# Nano103.net
KiCad netlist of a schematic drawn in Altium Designer
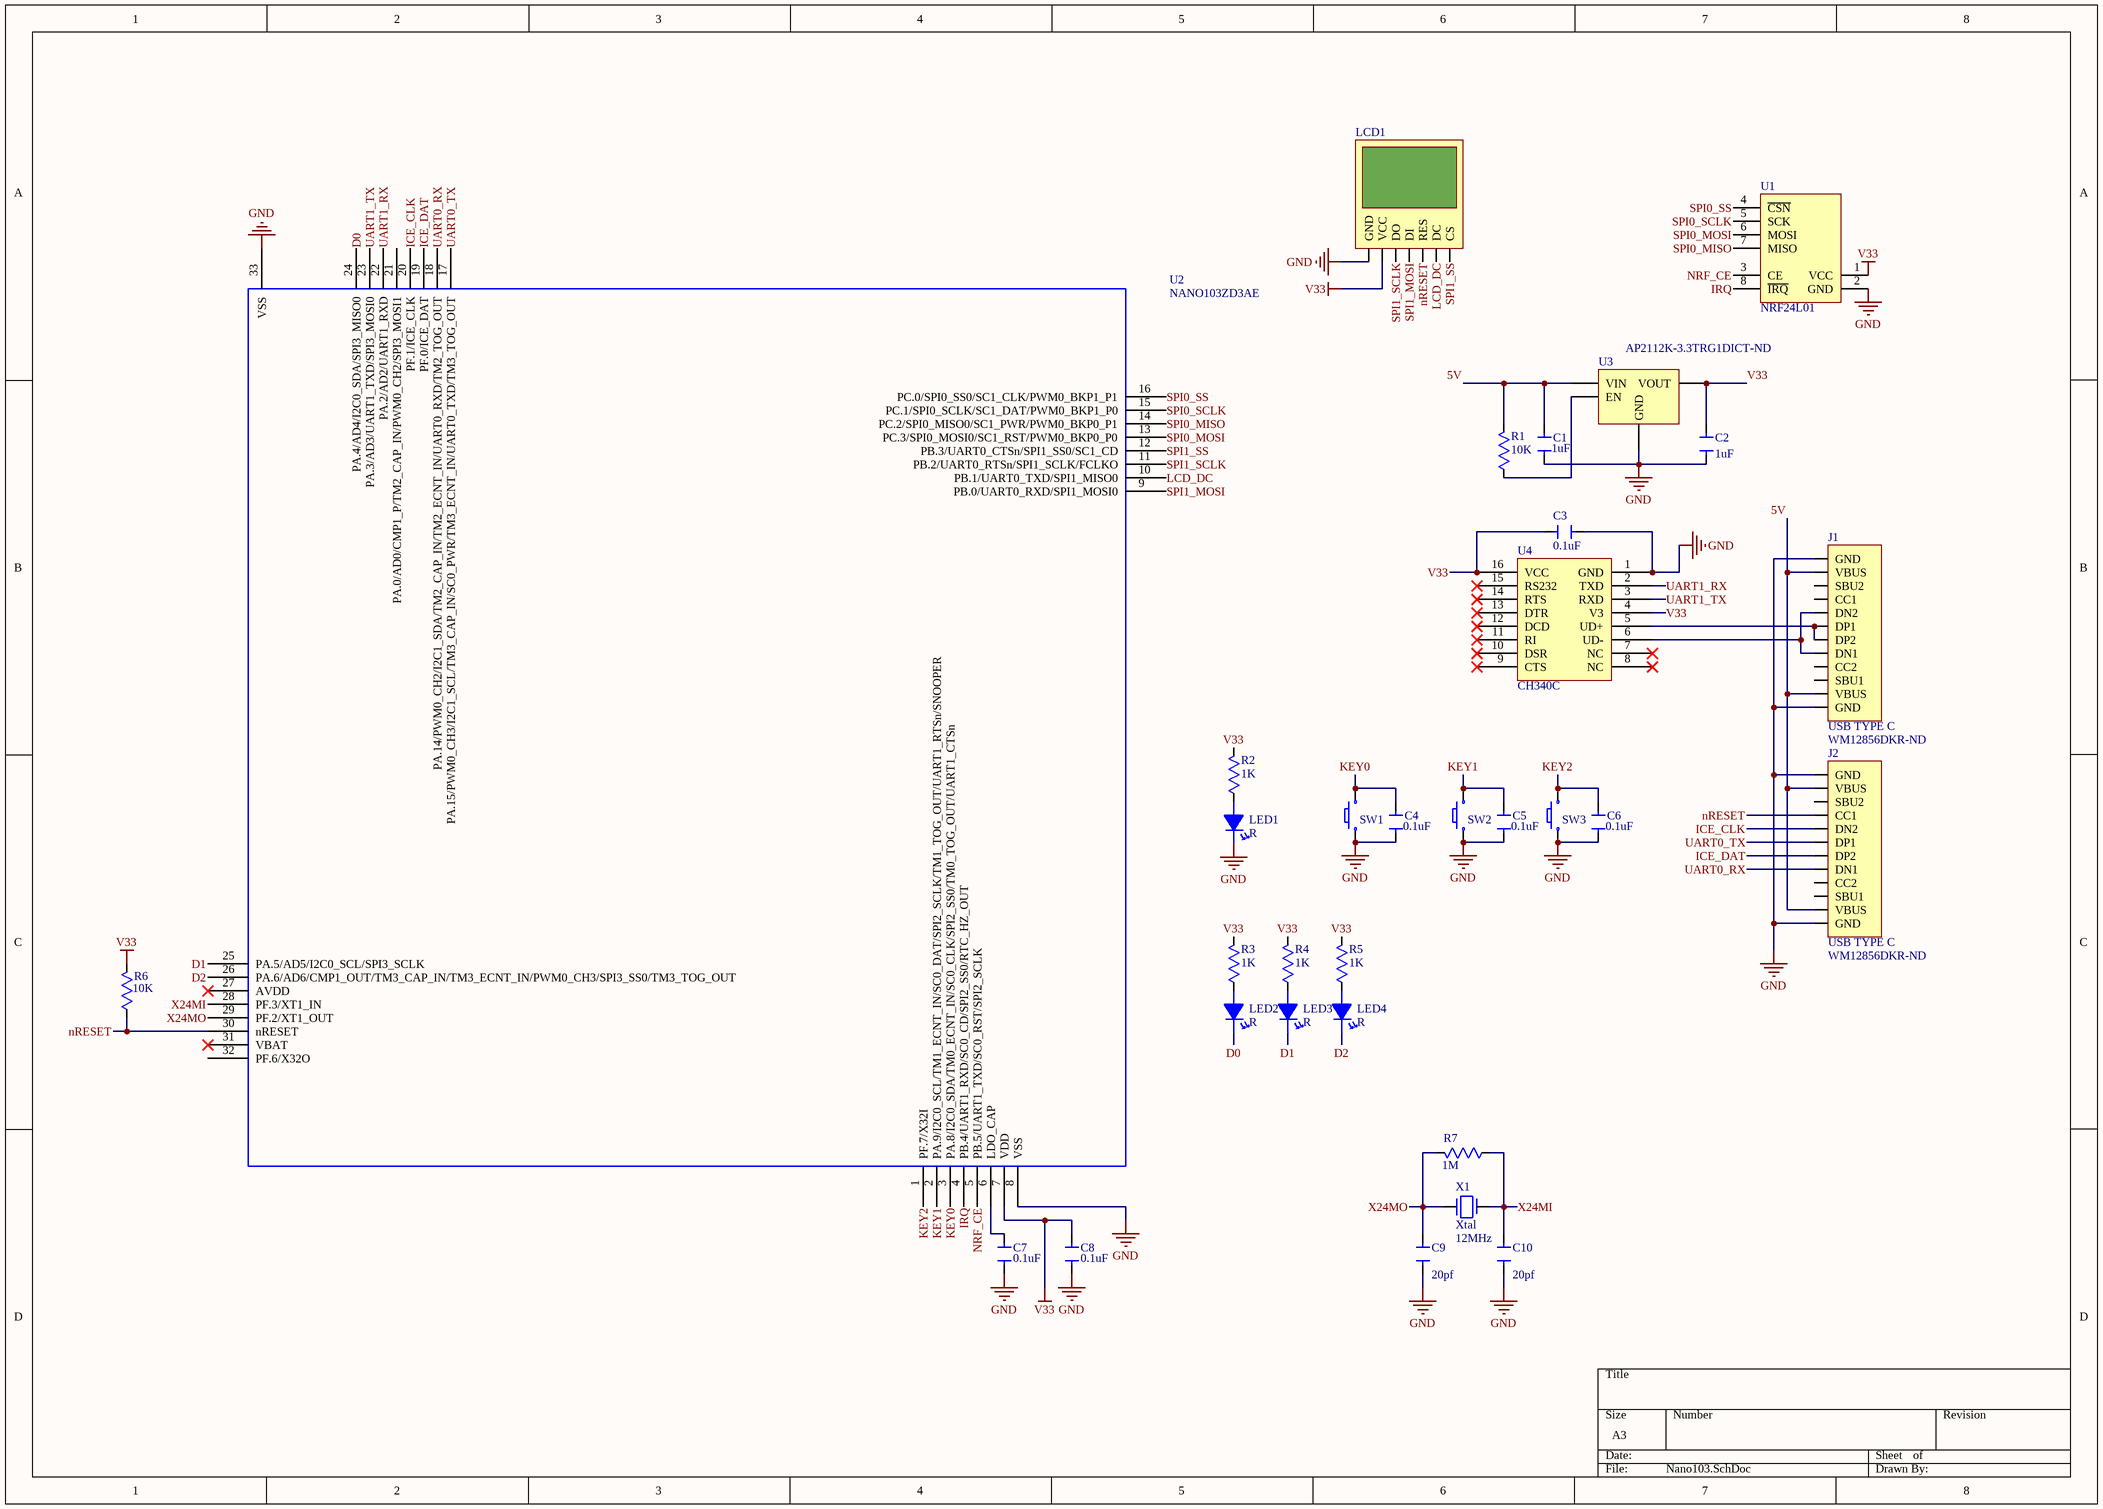
[diagram p0: Nano103.SchDoc]

(export (version "E")
  (design (tool "Eeschema 10.0.6"))
  (components
    (comp (ref "C1")
      (value "1uF")
      (footprint "CAP_0402")
      (fields (field (name "Comment") "Cap"))
      (libsource (lib "ZGR") (part "Cap"))
    )
    (comp (ref "C2")
      (value "1uF")
      (footprint "CAP_0402")
      (fields (field (name "Comment") "Cap"))
      (libsource (lib "ZGR") (part "Cap"))
    )
    (comp (ref "C3")
      (value "0.1uF")
      (footprint "CAP_0402")
      (fields (field (name "Comment") "Cap"))
      (libsource (lib "ZGR") (part "Cap"))
    )
    (comp (ref "C4")
      (value "0.1uF")
      (footprint "CAP_0402")
      (fields (field (name "Comment") "Cap"))
      (libsource (lib "ZGR") (part "Cap"))
    )
    (comp (ref "C5")
      (value "0.1uF")
      (footprint "CAP_0402")
      (fields (field (name "Comment") "Cap"))
      (libsource (lib "ZGR") (part "Cap"))
    )
    (comp (ref "C6")
      (value "0.1uF")
      (footprint "CAP_0402")
      (fields (field (name "Comment") "Cap"))
      (libsource (lib "ZGR") (part "Cap"))
    )
    (comp (ref "C7")
      (value "0.1uF")
      (footprint "CAP_0402")
      (fields (field (name "Comment") "Cap"))
      (libsource (lib "ZGR") (part "Cap"))
    )
    (comp (ref "C8")
      (value "0.1uF")
      (footprint "CAP_0402")
      (fields (field (name "Comment") "Cap"))
      (libsource (lib "ZGR") (part "Cap"))
    )
    (comp (ref "C9")
      (value "20pf")
      (footprint "CAP_0402")
      (fields (field (name "Comment") "Cap"))
      (libsource (lib "ZGR") (part "Cap"))
    )
    (comp (ref "C10")
      (value "20pf")
      (footprint "CAP_0402")
      (fields (field (name "Comment") "Cap"))
      (libsource (lib "ZGR") (part "Cap"))
    )
    (comp (ref "J1")
      (value "USB TYPE C")
      (footprint "USBC-SMD16F")
      (description "USB Shielded I/O Receptacle; Type C; Right Angle; Surface Mount; Gold over Nickel")
      (fields
        (field (name "MANUFACTURER") "Molex")
        (field (name "MANUFACTURER PART NUMBER") "105450-0101")
        (field (name "SUPPLIER PART NUMBER 1") "WM12856DKR-ND")
      )
      (libsource (lib "ZGR") (part "USB TYPE C"))
    )
    (comp (ref "J2")
      (value "USB TYPE C")
      (footprint "USBC-SMD16F")
      (description "USB Shielded I/O Receptacle; Type C; Right Angle; Surface Mount; Gold over Nickel")
      (fields
        (field (name "MANUFACTURER") "Molex")
        (field (name "MANUFACTURER PART NUMBER") "105450-0101")
        (field (name "SUPPLIER PART NUMBER 1") "WM12856DKR-ND")
      )
      (libsource (lib "ZGR") (part "USB TYPE C"))
    )
    (comp (ref "LCD1") (value "LCD096") (footprint "LCD096") (libsource (lib "ZGR") (part "LCD096")))
    (comp (ref "LED1") (value "R") (footprint "SMD-0603_LED") (libsource (lib "ZGR") (part "LED")))
    (comp (ref "LED2") (value "R") (footprint "SMD-0603_LED") (libsource (lib "ZGR") (part "LED")))
    (comp (ref "LED3") (value "R") (footprint "SMD-0603_LED") (libsource (lib "ZGR") (part "LED")))
    (comp (ref "LED4") (value "R") (footprint "SMD-0603_LED") (libsource (lib "ZGR") (part "LED")))
    (comp (ref "R1")
      (value "10K")
      (footprint "RES_0402")
      (fields (field (name "Comment") "Res"))
      (libsource (lib "ZGR") (part "Res"))
    )
    (comp (ref "R2")
      (value "1K")
      (footprint "RES_0402")
      (fields (field (name "Comment") "Res"))
      (libsource (lib "ZGR") (part "Res"))
    )
    (comp (ref "R3")
      (value "1K")
      (footprint "RES_0402")
      (fields (field (name "Comment") "Res"))
      (libsource (lib "ZGR") (part "Res"))
    )
    (comp (ref "R4")
      (value "1K")
      (footprint "RES_0402")
      (fields (field (name "Comment") "Res"))
      (libsource (lib "ZGR") (part "Res"))
    )
    (comp (ref "R5")
      (value "1K")
      (footprint "RES_0402")
      (fields (field (name "Comment") "Res"))
      (libsource (lib "ZGR") (part "Res"))
    )
    (comp (ref "R6")
      (value "10K")
      (footprint "RES_0402")
      (fields (field (name "Comment") "Res"))
      (libsource (lib "ZGR") (part "Res"))
    )
    (comp (ref "R7")
      (value "1M")
      (footprint "RES_0402")
      (fields (field (name "Comment") "Res"))
      (libsource (lib "ZGR") (part "Res"))
    )
    (comp (ref "SW1") (value "SPST") (footprint "ST01-111") (libsource (lib "ZGR") (part "Switch_Button1")))
    (comp (ref "SW2") (value "SPST") (footprint "ST01-111") (libsource (lib "ZGR") (part "Switch_Button1")))
    (comp (ref "SW3") (value "SPST") (footprint "ST01-111") (libsource (lib "ZGR") (part "Switch_Button1")))
    (comp (ref "U1")
      (value "NRF24L01")
      (footprint "NRF24L01P+PA+LNA+IPX")
      (libsource (lib "ZGR") (part "NRF24L01_module"))
    )
    (comp (ref "U2")
      (value "NANO103ZD3AE")
      (footprint "MCU_QFN_33_5x5")
      (libsource (lib "NUVOTON") (part "NANO103ZD3AE"))
    )
    (comp (ref "U3")
      (value "AP2112K-3.3TRG1")
      (footprint "SOT23-5")
      (description "IC REG LINEAR 3.3V 600MA SOT23-5")
      (fields
        (field (name "MANUFACTURER") "Diodes")
        (field (name "SUPPLIER PART NUMBER 1") "AP2112K-3.3TRG1DICT-ND")
      )
      (libsource (lib "ZGR") (part "AP2112K-3.3TRG1"))
    )
    (comp (ref "U4") (value "CH340C") (footprint "SOP-16") (libsource (lib "ZGR") (part "CH340C")))
    (comp (ref "X1")
      (value "Xtal")
      (footprint "2520S")
      (fields (field (name "ALTIUM_VALUE") "12MHz"))
      (libsource (lib "ZGR") (part "Xtal"))
    )
  )
  (nets
    (net (code "1") (name "/5V") (class "Default")
      (node (ref "C1") (pin "1") (pinfunction "1_1") (pintype "passive"))
      (node (ref "J1") (pin "11") (pinfunction "VBUS_11") (pintype "passive"))
      (node (ref "J1") (pin "2") (pinfunction "VBUS_2") (pintype "passive"))
      (node (ref "J2") (pin "11") (pinfunction "VBUS_11") (pintype "passive"))
      (node (ref "J2") (pin "2") (pinfunction "VBUS_2") (pintype "passive"))
      (node (ref "R1") (pin "1") (pinfunction "1_1") (pintype "passive"))
      (node (ref "U3") (pin "1") (pinfunction "VIN_1") (pintype "power_in"))
    )
    (net (code "3") (name "/D0") (class "Default")
      (node (ref "LED2") (pin "2") (pinfunction "2_2") (pintype "passive"))
      (node (ref "U2") (pin "24") (pinfunction "PA.4/AD4/I2C0_SDA/SPI3_MISO0_24") (pintype "passive"))
    )
    (net (code "4") (name "/D1") (class "Default")
      (node (ref "LED3") (pin "2") (pinfunction "2_2") (pintype "passive"))
      (node (ref "U2") (pin "25") (pinfunction "PA.5/AD5/I2C0_SCL/SPI3_SCLK_25") (pintype "passive"))
    )
    (net (code "5") (name "/D2") (class "Default")
      (node (ref "LED4") (pin "2") (pinfunction "2_2") (pintype "passive"))
      (node (ref "U2") (pin "26") (pinfunction "PA.6/AD6/CMP1_OUT/TM3_CAP_IN/TM3_ECNT_IN/PWM0_CH3/SPI3_SS0/TM3_TOG_OUT_26") (pintype "passive"))
    )
    (net (code "6") (name "/ICE_CLK") (class "Default")
      (node (ref "J2") (pin "5") (pinfunction "DN2_5") (pintype "passive"))
      (node (ref "U2") (pin "20") (pinfunction "PF.1/ICE_CLK_20") (pintype "passive"))
    )
    (net (code "7") (name "/ICE_DAT") (class "Default")
      (node (ref "J2") (pin "7") (pinfunction "DP2_7") (pintype "passive"))
      (node (ref "U2") (pin "19") (pinfunction "PF.0/ICE_DAT_19") (pintype "passive"))
    )
    (net (code "8") (name "/IRQ") (class "Default")
      (node (ref "U1") (pin "8") (pinfunction "~{IRQ}_8") (pintype "passive"))
      (node (ref "U2") (pin "4") (pinfunction "PB.4/UART1_RXD/SC0_CD/SPI2_SS0/RTC_HZ_OUT_4") (pintype "passive"))
    )
    (net (code "9") (name "/KEY0") (class "Default")
      (node (ref "C4") (pin "1") (pinfunction "1_1") (pintype "passive"))
      (node (ref "SW1") (pin "1") (pinfunction "1_1") (pintype "passive"))
      (node (ref "U2") (pin "3") (pinfunction "PA.8/I2C0_SDA/TM0_ECNT_IN/SC0_CLK/SPI2_SS0/TM0_TOG_OUT/UART1_CTSn_3") (pintype "passive"))
    )
    (net (code "10") (name "/KEY1") (class "Default")
      (node (ref "C5") (pin "1") (pinfunction "1_1") (pintype "passive"))
      (node (ref "SW2") (pin "1") (pinfunction "1_1") (pintype "passive"))
      (node (ref "U2") (pin "2") (pinfunction "PA.9/I2C0_SCL/TM1_ECNT_IN/SC0_DAT/SPI2_SCLK/TM1_TOG_OUT/UART1_RTSn/SNOOPER_2") (pintype "passive"))
    )
    (net (code "11") (name "/KEY2") (class "Default")
      (node (ref "C6") (pin "1") (pinfunction "1_1") (pintype "passive"))
      (node (ref "SW3") (pin "1") (pinfunction "1_1") (pintype "passive"))
      (node (ref "U2") (pin "1") (pinfunction "PF.7/X32I_1") (pintype "passive"))
    )
    (net (code "12") (name "/LCD_DC") (class "Default")
      (node (ref "LCD1") (pin "6") (pinfunction "DC_6") (pintype "passive"))
      (node (ref "U2") (pin "10") (pinfunction "PB.1/UART0_TXD/SPI1_MISO0_10") (pintype "passive"))
    )
    (net (code "13") (name "/NRF_CE") (class "Default")
      (node (ref "U1") (pin "3") (pinfunction "CE_3") (pintype "passive"))
      (node (ref "U2") (pin "5") (pinfunction "PB.5/UART1_TXD/SC0_RST/SPI2_SCLK_5") (pintype "passive"))
    )
    (net (code "14") (name "/SPI0_MISO") (class "Default")
      (node (ref "U1") (pin "7") (pinfunction "MISO_7") (pintype "passive"))
      (node (ref "U2") (pin "14") (pinfunction "PC.2/SPI0_MISO0/SC1_PWR/PWM0_BKP0_P1_14") (pintype "passive"))
    )
    (net (code "15") (name "/SPI0_MOSI") (class "Default")
      (node (ref "U1") (pin "6") (pinfunction "MOSI_6") (pintype "passive"))
      (node (ref "U2") (pin "13") (pinfunction "PC.3/SPI0_MOSI0/SC1_RST/PWM0_BKP0_P0_13") (pintype "passive"))
    )
    (net (code "16") (name "/SPI0_SCLK") (class "Default")
      (node (ref "U1") (pin "5") (pinfunction "SCK_5") (pintype "passive"))
      (node (ref "U2") (pin "15") (pinfunction "PC.1/SPI0_SCLK/SC1_DAT/PWM0_BKP1_P0_15") (pintype "passive"))
    )
    (net (code "17") (name "/SPI0_SS") (class "Default")
      (node (ref "U1") (pin "4") (pinfunction "~{CSN}_4") (pintype "passive"))
      (node (ref "U2") (pin "16") (pinfunction "PC.0/SPI0_SS0/SC1_CLK/PWM0_BKP1_P1_16") (pintype "passive"))
    )
    (net (code "18") (name "/SPI1_MOSI") (class "Default")
      (node (ref "LCD1") (pin "4") (pinfunction "DI_4") (pintype "passive"))
      (node (ref "U2") (pin "9") (pinfunction "PB.0/UART0_RXD/SPI1_MOSI0_9") (pintype "passive"))
    )
    (net (code "19") (name "/SPI1_SCLK") (class "Default")
      (node (ref "LCD1") (pin "3") (pinfunction "DO_3") (pintype "passive"))
      (node (ref "U2") (pin "11") (pinfunction "PB.2/UART0_RTSn/SPI1_SCLK/FCLKO_11") (pintype "passive"))
    )
    (net (code "20") (name "/SPI1_SS") (class "Default")
      (node (ref "LCD1") (pin "7") (pinfunction "CS_7") (pintype "passive"))
      (node (ref "U2") (pin "12") (pinfunction "PB.3/UART0_CTSn/SPI1_SS0/SC1_CD_12") (pintype "passive"))
    )
    (net (code "21") (name "/UART0_RX") (class "Default")
      (node (ref "J2") (pin "8") (pinfunction "DN1_8") (pintype "passive"))
      (node (ref "U2") (pin "18") (pinfunction "PA.14/PWM0_CH2/I2C1_SDA/TM2_CAP_IN/TM2_ECNT_IN/UART0_RXD/TM2_TOG_OUT_18") (pintype "passive"))
    )
    (net (code "22") (name "/UART0_TX") (class "Default")
      (node (ref "J2") (pin "6") (pinfunction "DP1_6") (pintype "passive"))
      (node (ref "U2") (pin "17") (pinfunction "PA.15/PWM0_CH3/I2C1_SCL/TM3_CAP_IN/SC0_PWR/TM3_ECNT_IN/UART0_TXD/TM3_TOG_OUT_17") (pintype "passive"))
    )
    (net (code "23") (name "/UART1_RX") (class "Default")
      (node (ref "U2") (pin "22") (pinfunction "PA.2/AD2/UART1_RXD_22") (pintype "passive"))
      (node (ref "U4") (pin "2") (pinfunction "TXD_2") (pintype "passive"))
    )
    (net (code "24") (name "/UART1_TX") (class "Default")
      (node (ref "U2") (pin "23") (pinfunction "PA.3/AD3/UART1_TXD/SPI3_MOSI0_23") (pintype "passive"))
      (node (ref "U4") (pin "3") (pinfunction "RXD_3") (pintype "passive"))
    )
    (net (code "25") (name "/X24MI") (class "Default")
      (node (ref "C10") (pin "1") (pinfunction "1_1") (pintype "passive"))
      (node (ref "R7") (pin "2") (pinfunction "2_2") (pintype "passive"))
      (node (ref "U2") (pin "28") (pinfunction "PF.3/XT1_IN_28") (pintype "passive"))
      (node (ref "X1") (pin "1") (pintype "passive"))
    )
    (net (code "26") (name "/X24MO") (class "Default")
      (node (ref "C9") (pin "1") (pinfunction "1_1") (pintype "passive"))
      (node (ref "R7") (pin "1") (pinfunction "1_1") (pintype "passive"))
      (node (ref "U2") (pin "29") (pinfunction "PF.2/XT1_OUT_29") (pintype "passive"))
      (node (ref "X1") (pin "2") (pintype "passive"))
    )
    (net (code "27") (name "/nRESET") (class "Default")
      (node (ref "J2") (pin "4") (pinfunction "CC1_4") (pintype "passive"))
      (node (ref "LCD1") (pin "5") (pinfunction "RES_5") (pintype "passive"))
      (node (ref "R6") (pin "2") (pinfunction "2_2") (pintype "passive"))
      (node (ref "U2") (pin "30") (pinfunction "nRESET_30") (pintype "passive"))
    )
    (net (code "28") (name "GND") (class "Default")
      (node (ref "C1") (pin "2") (pinfunction "2_2") (pintype "passive"))
      (node (ref "C10") (pin "2") (pinfunction "2_2") (pintype "passive"))
      (node (ref "C2") (pin "2") (pinfunction "2_2") (pintype "passive"))
      (node (ref "C3") (pin "2") (pinfunction "2_2") (pintype "passive"))
      (node (ref "C4") (pin "2") (pinfunction "2_2") (pintype "passive"))
      (node (ref "C5") (pin "2") (pinfunction "2_2") (pintype "passive"))
      (node (ref "C6") (pin "2") (pinfunction "2_2") (pintype "passive"))
      (node (ref "C7") (pin "2") (pinfunction "2_2") (pintype "passive"))
      (node (ref "C8") (pin "2") (pinfunction "2_2") (pintype "passive"))
      (node (ref "C9") (pin "2") (pinfunction "2_2") (pintype "passive"))
      (node (ref "J1") (pin "1") (pinfunction "GND_1") (pintype "passive"))
      (node (ref "J1") (pin "12") (pinfunction "GND_12") (pintype "passive"))
      (node (ref "J2") (pin "1") (pinfunction "GND_1") (pintype "passive"))
      (node (ref "J2") (pin "12") (pinfunction "GND_12") (pintype "passive"))
      (node (ref "LCD1") (pin "1") (pinfunction "GND_1") (pintype "passive"))
      (node (ref "LED1") (pin "2") (pinfunction "2_2") (pintype "passive"))
      (node (ref "SW1") (pin "2") (pinfunction "2_2") (pintype "passive"))
      (node (ref "SW2") (pin "2") (pinfunction "2_2") (pintype "passive"))
      (node (ref "SW3") (pin "2") (pinfunction "2_2") (pintype "passive"))
      (node (ref "U1") (pin "2") (pinfunction "GND_2") (pintype "power_in"))
      (node (ref "U2") (pin "33") (pinfunction "VSS_33") (pintype "passive"))
      (node (ref "U2") (pin "8") (pinfunction "VSS_8") (pintype "passive"))
      (node (ref "U3") (pin "3") (pinfunction "GND_3") (pintype "power_in"))
      (node (ref "U4") (pin "1") (pinfunction "GND_1") (pintype "passive"))
    )
    (net (code "29") (name "Net-(J1-DN1)") (class "Default")
      (node (ref "J1") (pin "5") (pinfunction "DN2_5") (pintype "passive"))
      (node (ref "J1") (pin "8") (pinfunction "DN1_8") (pintype "passive"))
      (node (ref "U4") (pin "6") (pinfunction "UD-_6") (pintype "passive"))
    )
    (net (code "30") (name "Net-(J1-DP1)") (class "Default")
      (node (ref "J1") (pin "6") (pinfunction "DP1_6") (pintype "passive"))
      (node (ref "J1") (pin "7") (pinfunction "DP2_7") (pintype "passive"))
      (node (ref "U4") (pin "5") (pinfunction "UD+_5") (pintype "passive"))
    )
    (net (code "31") (name "Net-(LED1-Pad1)") (class "Default")
      (node (ref "LED1") (pin "1") (pinfunction "1_1") (pintype "passive"))
      (node (ref "R2") (pin "2") (pinfunction "2_2") (pintype "passive"))
    )
    (net (code "32") (name "Net-(LED2-Pad1)") (class "Default")
      (node (ref "LED2") (pin "1") (pinfunction "1_1") (pintype "passive"))
      (node (ref "R3") (pin "2") (pinfunction "2_2") (pintype "passive"))
    )
    (net (code "33") (name "Net-(LED3-Pad1)") (class "Default")
      (node (ref "LED3") (pin "1") (pinfunction "1_1") (pintype "passive"))
      (node (ref "R4") (pin "2") (pinfunction "2_2") (pintype "passive"))
    )
    (net (code "34") (name "Net-(LED4-Pad1)") (class "Default")
      (node (ref "LED4") (pin "1") (pinfunction "1_1") (pintype "passive"))
      (node (ref "R5") (pin "2") (pinfunction "2_2") (pintype "passive"))
    )
    (net (code "35") (name "Net-(U2-LDO_CAP)") (class "Default")
      (node (ref "C7") (pin "1") (pinfunction "1_1") (pintype "passive"))
      (node (ref "U2") (pin "6") (pinfunction "LDO_CAP_6") (pintype "passive"))
    )
    (net (code "36") (name "Net-(U3-EN)") (class "Default")
      (node (ref "R1") (pin "2") (pinfunction "2_2") (pintype "passive"))
      (node (ref "U3") (pin "2") (pinfunction "EN_2") (pintype "passive"))
    )
    (net (code "37") (name "V33") (class "Default")
      (node (ref "C2") (pin "1") (pinfunction "1_1") (pintype "passive"))
      (node (ref "C3") (pin "1") (pinfunction "1_1") (pintype "passive"))
      (node (ref "C8") (pin "1") (pinfunction "1_1") (pintype "passive"))
      (node (ref "LCD1") (pin "2") (pinfunction "VCC_2") (pintype "passive"))
      (node (ref "R2") (pin "1") (pinfunction "1_1") (pintype "passive"))
      (node (ref "R3") (pin "1") (pinfunction "1_1") (pintype "passive"))
      (node (ref "R4") (pin "1") (pinfunction "1_1") (pintype "passive"))
      (node (ref "R5") (pin "1") (pinfunction "1_1") (pintype "passive"))
      (node (ref "R6") (pin "1") (pinfunction "1_1") (pintype "passive"))
      (node (ref "U1") (pin "1") (pinfunction "VCC_1") (pintype "power_in"))
      (node (ref "U2") (pin "7") (pinfunction "VDD_7") (pintype "passive"))
      (node (ref "U3") (pin "4") (pinfunction "VOUT_4") (pintype "power_in"))
      (node (ref "U4") (pin "16") (pinfunction "VCC_16") (pintype "passive"))
      (node (ref "U4") (pin "4") (pinfunction "V3_4") (pintype "passive"))
    )
    (net (code "38") (name "unconnected-(J1-CC1-Pad4)") (class "Default")
      (node (ref "J1") (pin "4") (pinfunction "CC1_4") (pintype "passive"))
    )
    (net (code "39") (name "unconnected-(J1-CC2-Pad9)") (class "Default")
      (node (ref "J1") (pin "9") (pinfunction "CC2_9") (pintype "passive"))
    )
    (net (code "40") (name "unconnected-(J1-SBU1-Pad10)") (class "Default")
      (node (ref "J1") (pin "10") (pinfunction "SBU1_10") (pintype "passive"))
    )
    (net (code "41") (name "unconnected-(J1-SBU2-Pad3)") (class "Default")
      (node (ref "J1") (pin "3") (pinfunction "SBU2_3") (pintype "passive"))
    )
    (net (code "42") (name "unconnected-(J2-CC2-Pad9)") (class "Default")
      (node (ref "J2") (pin "9") (pinfunction "CC2_9") (pintype "passive"))
    )
    (net (code "43") (name "unconnected-(J2-SBU1-Pad10)") (class "Default")
      (node (ref "J2") (pin "10") (pinfunction "SBU1_10") (pintype "passive"))
    )
    (net (code "44") (name "unconnected-(J2-SBU2-Pad3)") (class "Default")
      (node (ref "J2") (pin "3") (pinfunction "SBU2_3") (pintype "passive"))
    )
    (net (code "45") (name "unconnected-(U2-AVDD-Pad27)") (class "Default")
      (node (ref "U2") (pin "27") (pinfunction "AVDD_27") (pintype "passive+no_connect"))
    )
    (net (code "46") (name "unconnected-(U2-PA.0{slash}AD0{slash}CMP1_P{slash}TM2_CAP_IN{slash}PWM0_CH2{slash}SPI3_MOSI1-Pad21)") (class "Default")
      (node (ref "U2") (pin "21") (pinfunction "PA.0/AD0/CMP1_P/TM2_CAP_IN/PWM0_CH2/SPI3_MOSI1_21") (pintype "passive"))
    )
    (net (code "47") (name "unconnected-(U2-PF.6{slash}X32O-Pad32)") (class "Default")
      (node (ref "U2") (pin "32") (pinfunction "PF.6/X32O_32") (pintype "passive"))
    )
    (net (code "48") (name "unconnected-(U2-VBAT-Pad31)") (class "Default")
      (node (ref "U2") (pin "31") (pinfunction "VBAT_31") (pintype "passive+no_connect"))
    )
    (net (code "49") (name "unconnected-(U4-CTS-Pad9)") (class "Default")
      (node (ref "U4") (pin "9") (pinfunction "CTS_9") (pintype "passive+no_connect"))
    )
    (net (code "50") (name "unconnected-(U4-DCD-Pad12)") (class "Default")
      (node (ref "U4") (pin "12") (pinfunction "DCD_12") (pintype "passive+no_connect"))
    )
    (net (code "51") (name "unconnected-(U4-DSR-Pad10)") (class "Default")
      (node (ref "U4") (pin "10") (pinfunction "DSR_10") (pintype "passive+no_connect"))
    )
    (net (code "52") (name "unconnected-(U4-DTR-Pad13)") (class "Default")
      (node (ref "U4") (pin "13") (pinfunction "DTR_13") (pintype "passive+no_connect"))
    )
    (net (code "53") (name "unconnected-(U4-NC-Pad7)") (class "Default")
      (node (ref "U4") (pin "7") (pinfunction "NC_7") (pintype "passive+no_connect"))
    )
    (net (code "54") (name "unconnected-(U4-NC-Pad8)") (class "Default")
      (node (ref "U4") (pin "8") (pinfunction "NC_8") (pintype "passive+no_connect"))
    )
    (net (code "55") (name "unconnected-(U4-RI-Pad11)") (class "Default")
      (node (ref "U4") (pin "11") (pinfunction "RI_11") (pintype "passive+no_connect"))
    )
    (net (code "56") (name "unconnected-(U4-RS232-Pad15)") (class "Default")
      (node (ref "U4") (pin "15") (pinfunction "RS232_15") (pintype "passive+no_connect"))
    )
    (net (code "57") (name "unconnected-(U4-RTS-Pad14)") (class "Default")
      (node (ref "U4") (pin "14") (pinfunction "RTS_14") (pintype "passive+no_connect"))
    )
  )
)
